# Power.net
KiCad netlist of a schematic drawn in Altium Designer
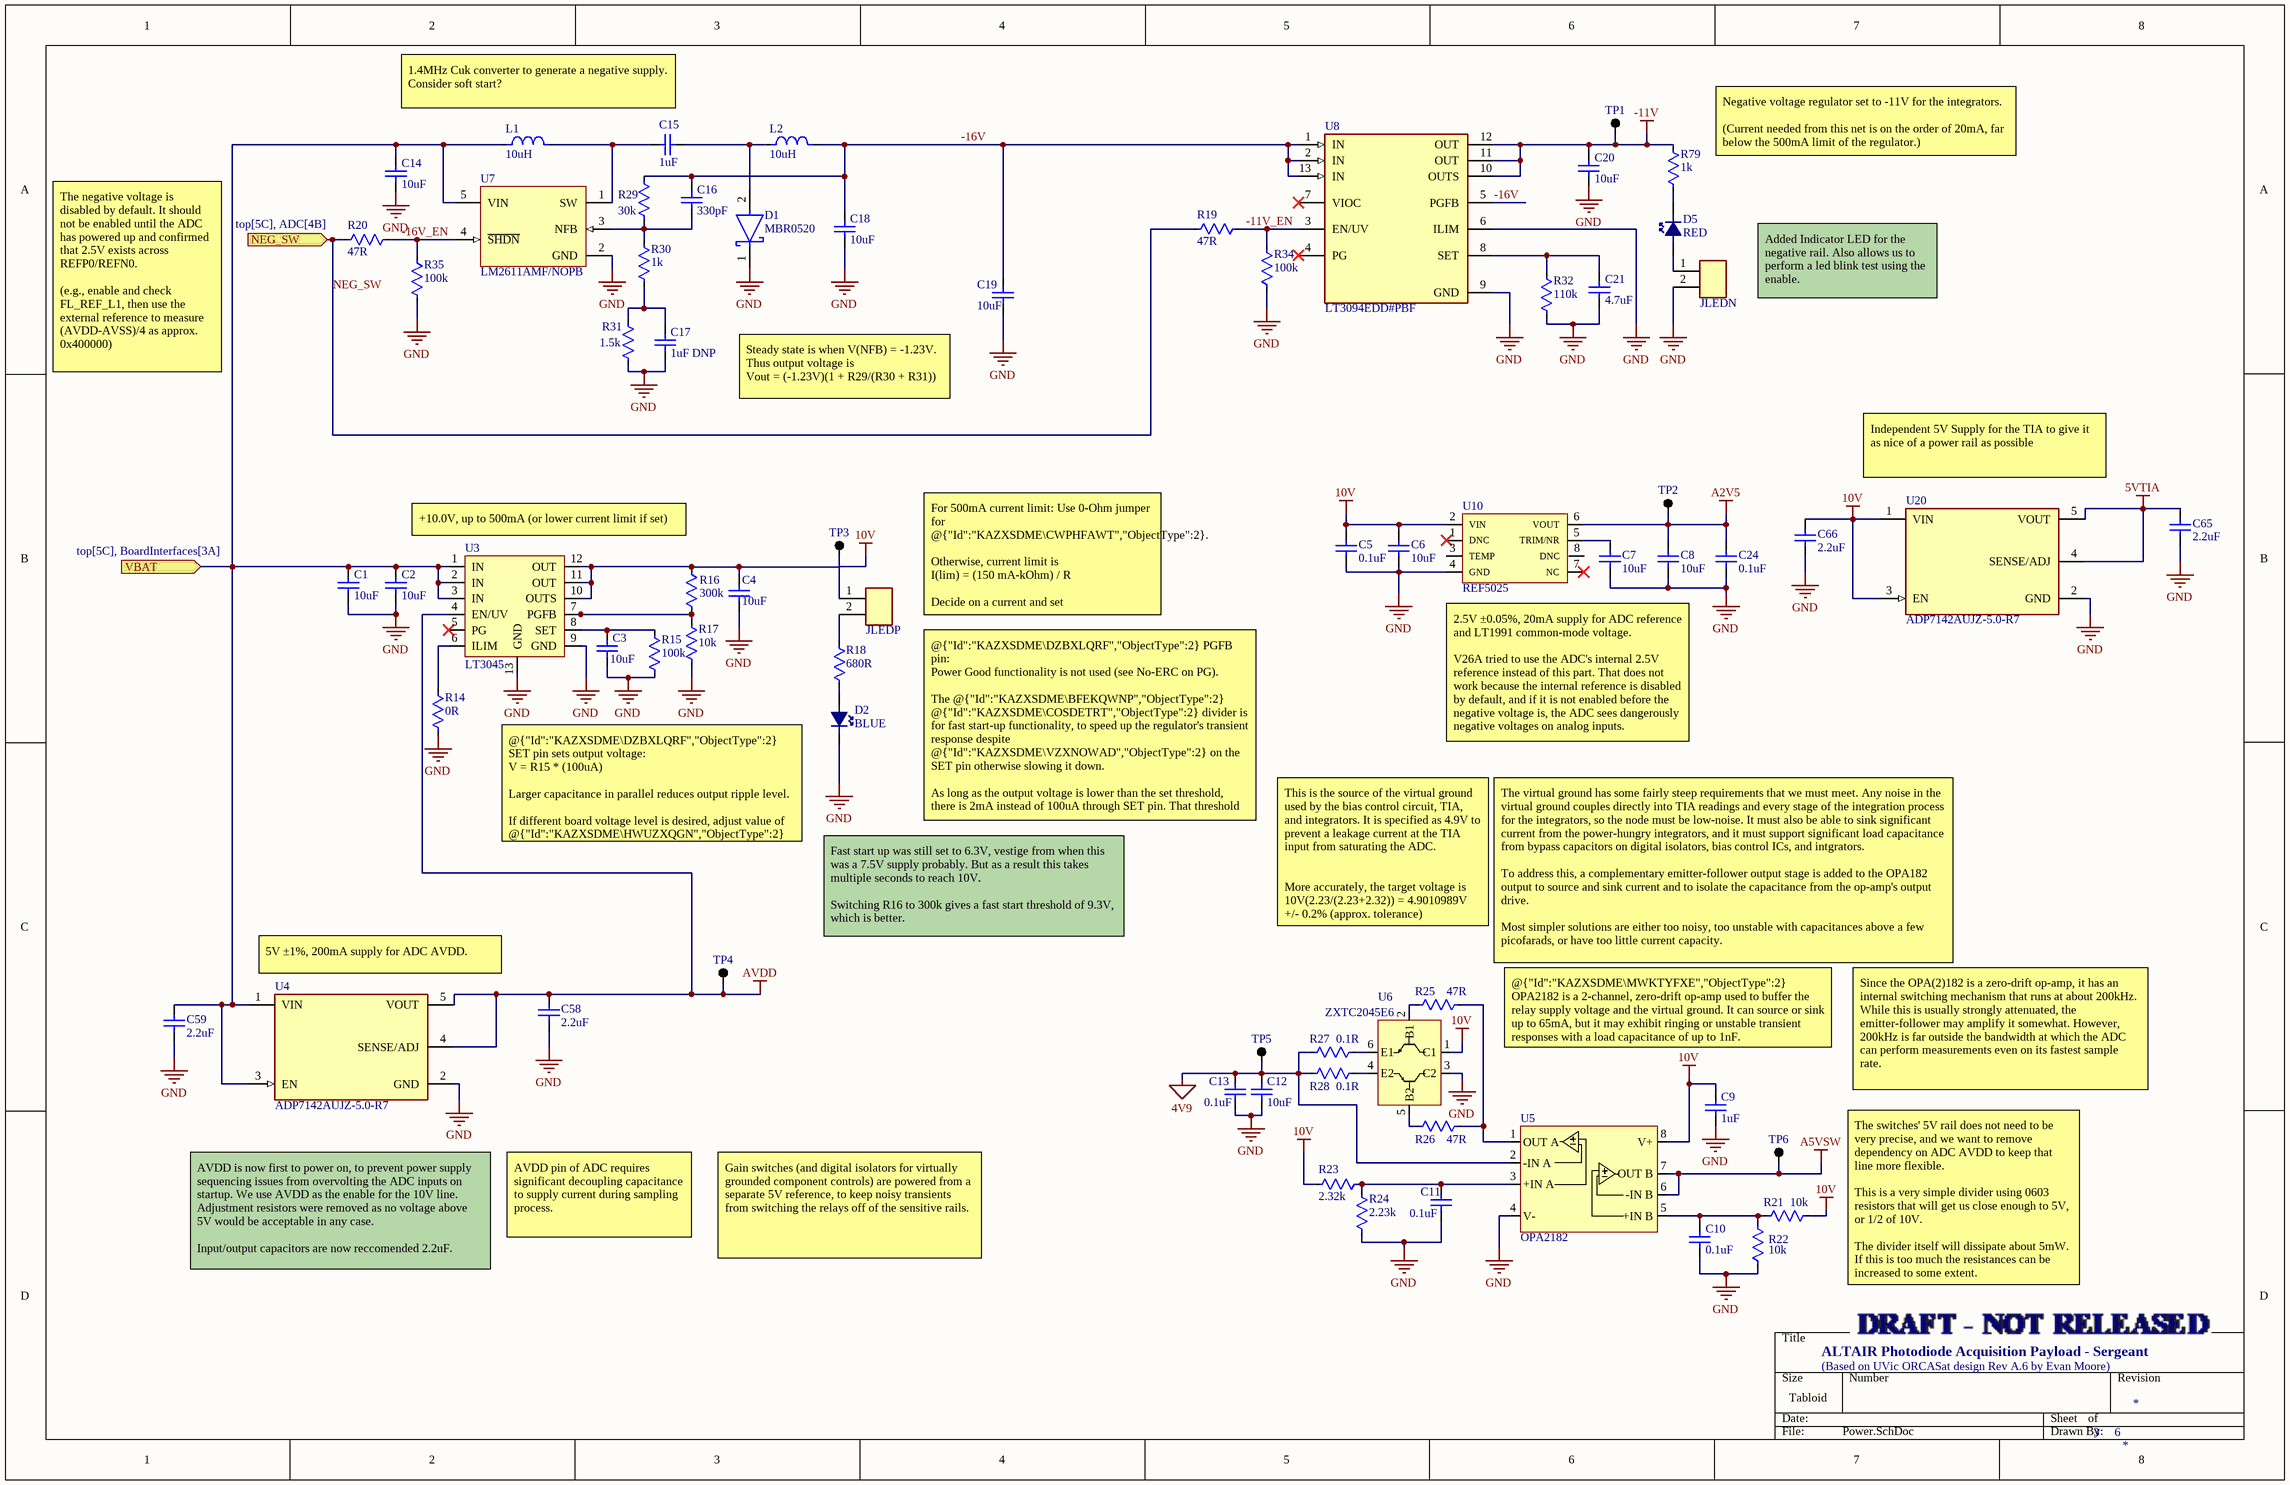
[diagram p0: Power.SchDoc]

(export (version "E")
  (design (tool "Eeschema 10.0.6"))
  (components
    (comp (ref "C1")
      (value "10uF")
      (footprint "CAP 1206 IPC LOW DENSITY")
      (description "Murata GRT319R6YA106KE01D - Cap Ceramic 10uF 35V X5R 10% Pad SMD 1206 85C Automotive T/R")
      (fields (field (name "MF") "Murata") (field (name "MP") "GRT319R6YA106KE01D"))
      (libsource (lib "ALTAIR_PD_Capacitors") (part "CAP"))
    )
    (comp (ref "C2")
      (value "10uF")
      (footprint "CAP 1206 IPC LOW DENSITY")
      (description "Murata GRT319R6YA106KE01D - Cap Ceramic 10uF 35V X5R 10% Pad SMD 1206 85C Automotive T/R")
      (fields (field (name "MF") "Murata") (field (name "MP") "GRT319R6YA106KE01D"))
      (libsource (lib "ALTAIR_PD_Capacitors") (part "CAP"))
    )
    (comp (ref "C3")
      (value "10uF")
      (footprint "CAP 1206 IPC LOW DENSITY")
      (description "Murata GRT319R6YA106KE01D - Cap Ceramic 10uF 35V X5R 10% Pad SMD 1206 85C Automotive T/R")
      (fields (field (name "MF") "Murata") (field (name "MP") "GRT319R6YA106KE01D"))
      (libsource (lib "ALTAIR_PD_Capacitors") (part "CAP"))
    )
    (comp (ref "C4")
      (value "10uF")
      (footprint "CAP 1206 IPC LOW DENSITY")
      (description "Murata GRT319R6YA106KE01D - Cap Ceramic 10uF 35V X5R 10% Pad SMD 1206 85C Automotive T/R")
      (fields (field (name "MF") "Murata") (field (name "MP") "GRT319R6YA106KE01D"))
      (libsource (lib "ALTAIR_PD_Capacitors") (part "CAP"))
    )
    (comp (ref "C5")
      (value "0.1uF")
      (footprint "CAP 0603 IPC MID DENSITY")
      (description "Kemet C0603C104K5RACAUTO - Cap Ceramic 0.1uF 50V X7R 10% 0603 125C Paper T/R")
      (fields (field (name "MF") "Kemet") (field (name "MP") "C0603C104K5RACAUTO"))
      (libsource (lib "ALTAIR_PD_Capacitors") (part "CAP"))
    )
    (comp (ref "C6")
      (value "10uF")
      (footprint "CAP 0805 IPC MID DENSITY")
      (description "Murata GRM21BR61E106KA73L - Cap Ceramic 10uF 10% 25V X5R 0805")
      (fields (field (name "MF") "Murata") (field (name "MP") "GRM21BR61E106KA73L"))
      (libsource (lib "ALTAIR_PD_Capacitors") (part "CAP"))
    )
    (comp (ref "C7")
      (value "10uF")
      (footprint "CAP 0805 IPC MID DENSITY")
      (description "Murata GRM21BR61E106KA73L - Cap Ceramic 10uF 10% 25V X5R 0805")
      (fields (field (name "MF") "Murata") (field (name "MP") "GRM21BR61E106KA73L"))
      (libsource (lib "ALTAIR_PD_Capacitors") (part "CAP"))
    )
    (comp (ref "C8")
      (value "10uF")
      (footprint "CAP 0805 IPC MID DENSITY")
      (description "Murata GRM21BR61E106KA73L - Cap Ceramic 10uF 10% 25V X5R 0805")
      (fields (field (name "MF") "Murata") (field (name "MP") "GRM21BR61E106KA73L"))
      (libsource (lib "ALTAIR_PD_Capacitors") (part "CAP"))
    )
    (comp (ref "C9")
      (value "1uF")
      (footprint "CAP 0603 IPC MID DENSITY")
      (description "Murata GRT188R61H105KE13D - Cap MLCC AEC-Q200 X5R 1uF 50V 0603")
      (fields (field (name "MF") "Murata") (field (name "MP") "GRT188R61H105KE13D"))
      (libsource (lib "ALTAIR_PD_Capacitors") (part "CAP"))
    )
    (comp (ref "C10")
      (value "0.1uF")
      (footprint "CAP 0603 IPC MID DENSITY")
      (description "Kemet C0603C104K5RACAUTO - Cap Ceramic 0.1uF 50V X7R 10% 0603 125C Paper T/R")
      (fields (field (name "MF") "Kemet") (field (name "MP") "C0603C104K5RACAUTO"))
      (libsource (lib "ALTAIR_PD_Capacitors") (part "CAP"))
    )
    (comp (ref "C11")
      (value "0.1uF")
      (footprint "CAP 0603 IPC MID DENSITY")
      (description "Kemet C0603C104K5RACAUTO - Cap Ceramic 0.1uF 50V X7R 10% 0603 125C Paper T/R")
      (fields (field (name "MF") "Kemet") (field (name "MP") "C0603C104K5RACAUTO"))
      (libsource (lib "ALTAIR_PD_Capacitors") (part "CAP"))
    )
    (comp (ref "C12")
      (value "10uF")
      (footprint "CAP 1206 IPC LOW DENSITY")
      (description "Murata GRT319R6YA106KE01D - Cap Ceramic 10uF 35V X5R 10% Pad SMD 1206 85C Automotive T/R")
      (fields (field (name "MF") "Murata") (field (name "MP") "GRT319R6YA106KE01D"))
      (libsource (lib "ALTAIR_PD_Capacitors") (part "CAP"))
    )
    (comp (ref "C13")
      (value "0.1uF")
      (footprint "CAP 0603 IPC MID DENSITY")
      (description "Kemet C0603C104K5RACAUTO - Cap Ceramic 0.1uF 50V X7R 10% 0603 125C Paper T/R")
      (fields (field (name "MF") "Kemet") (field (name "MP") "C0603C104K5RACAUTO"))
      (libsource (lib "ALTAIR_PD_Capacitors") (part "CAP"))
    )
    (comp (ref "C14")
      (value "10uF")
      (footprint "CAP 0805 IPC MID DENSITY")
      (description "Murata GRM21BR61E106KA73L - Cap Ceramic 10uF 10% 25V X5R 0805")
      (fields (field (name "MF") "Murata") (field (name "MP") "GRM21BR61E106KA73L"))
      (libsource (lib "ALTAIR_PD_Capacitors") (part "CAP"))
    )
    (comp (ref "C15")
      (value "1uF")
      (footprint "CAP 0603 IPC MID DENSITY")
      (description "Murata GRT188R61H105KE13D - Cap MLCC AEC-Q200 X5R 1uF 50V 0603")
      (fields (field (name "MF") "Murata") (field (name "MP") "GRT188R61H105KE13D"))
      (libsource (lib "ALTAIR_PD_Capacitors") (part "CAP"))
    )
    (comp (ref "C16")
      (value "330pF")
      (footprint "CAP 1206 NON-IPC KEMET NP0")
      (description "Kemet C1206C331J5GACTU - Cap Ceramic 330pF 50V 5% NP0 1206")
      (fields (field (name "MF") "Kemet") (field (name "MP") "C1206C331J5GACTU"))
      (libsource (lib "ALTAIR_PD_Capacitors") (part "CAP"))
    )
    (comp (ref "C17")
      (value "1uF DNP")
      (footprint "CAP 0603 IPC MID DENSITY")
      (description "Murata GRT188R61H105KE13D - Cap MLCC AEC-Q200 X5R 1uF 50V 0603")
      (fields (field (name "MF") "Murata") (field (name "MP") "GRT188R61H105KE13D"))
      (libsource (lib "ALTAIR_PD_Capacitors") (part "CAP"))
    )
    (comp (ref "C18")
      (value "10uF")
      (footprint "CAP 0805 IPC MID DENSITY")
      (description "Murata GRM21BR61E106KA73L - Cap Ceramic 10uF 10% 25V X5R 0805")
      (fields (field (name "MF") "Murata") (field (name "MP") "GRM21BR61E106KA73L"))
      (libsource (lib "ALTAIR_PD_Capacitors") (part "CAP"))
    )
    (comp (ref "C19")
      (value "10uF")
      (footprint "CAP 0805 IPC MID DENSITY")
      (description "Murata GRM21BR61E106KA73L - Cap Ceramic 10uF 10% 25V X5R 0805")
      (fields (field (name "MF") "Murata") (field (name "MP") "GRM21BR61E106KA73L"))
      (libsource (lib "ALTAIR_PD_Capacitors") (part "CAP"))
    )
    (comp (ref "C20")
      (value "10uF")
      (footprint "CAP 0805 IPC MID DENSITY")
      (description "Murata GRM21BR61E106KA73L - Cap Ceramic 10uF 10% 25V X5R 0805")
      (fields (field (name "MF") "Murata") (field (name "MP") "GRM21BR61E106KA73L"))
      (libsource (lib "ALTAIR_PD_Capacitors") (part "CAP"))
    )
    (comp (ref "C21")
      (value "4.7uF")
      (footprint "CAP 0805 NON-IPC KEMET X5R")
      (description "Kemet C0805C475K8PACTU - Cap Ceramic 4.7uF 10V X5R 0805")
      (fields (field (name "MF") "Kemet") (field (name "MP") "C0805C475K8PACTU"))
      (libsource (lib "ALTAIR_PD_Capacitors") (part "CAP"))
    )
    (comp (ref "C24")
      (value "0.1uF")
      (footprint "CAP 0603 IPC MID DENSITY")
      (description "Kemet C0603C104K5RACAUTO - Cap Ceramic 0.1uF 50V X7R 10% 0603 125C Paper T/R")
      (fields (field (name "MF") "Kemet") (field (name "MP") "C0603C104K5RACAUTO"))
      (libsource (lib "ALTAIR_PD_Capacitors") (part "CAP"))
    )
    (comp (ref "C58")
      (value "2.2uF")
      (footprint "CAP 1206 UNKNOWN")
      (description "Cap, Nonpolar, Any, Must choose footprint manually")
      (libsource (lib "ALTAIR_PD_Capacitors") (part "CAP"))
    )
    (comp (ref "C59")
      (value "2.2uF")
      (footprint "CAP 1206 UNKNOWN")
      (description "Cap, Nonpolar, Any, Must choose footprint manually")
      (libsource (lib "ALTAIR_PD_Capacitors") (part "CAP"))
    )
    (comp (ref "C65")
      (value "2.2uF")
      (footprint "CAP 1206 UNKNOWN")
      (description "Cap, Nonpolar, Any, Must choose footprint manually")
      (libsource (lib "ALTAIR_PD_Capacitors") (part "CAP"))
    )
    (comp (ref "C66")
      (value "2.2uF")
      (footprint "CAP 1206 UNKNOWN")
      (description "Cap, Nonpolar, Any, Must choose footprint manually")
      (libsource (lib "ALTAIR_PD_Capacitors") (part "CAP"))
    )
    (comp (ref "D1")
      (value "MBR0520")
      (footprint "SOD-123 ONSEMI SMALL PADS")
      (description "DIODE SCHOTTKY 20V 500MA SOD123")
      (fields (field (name "MF") "onsemi") (field (name "MP") "MBR0520LT1G"))
      (libsource (lib "ALTAIR_PD_Diodes") (part "Schottky"))
    )
    (comp (ref "D2")
      (value "BLUE")
      (footprint "LED 0603 MID DENSITY")
      (description "LED BLUE CLEAR 0603 SMD")
      (fields (field (name "MF") "Wurth Electronics") (field (name "MP") "150060BS75000"))
      (libsource (lib "ALTAIR_PD_Diodes") (part "LED-blue"))
    )
    (comp (ref "D5")
      (value "RED")
      (footprint "LED 0603 MID DENSITY")
      (description "LED BLUE CLEAR 0603 SMD")
      (fields (field (name "MF") "Wurth Electronics") (field (name "MP") "150060BS75000"))
      (libsource (lib "ALTAIR_PD_Diodes") (part "LED-blue"))
    )
    (comp (ref "JLEDN")
      (value "JLED")
      (footprint "JUMPER 2POS 1MM PITCH THT")
      (description "2x1 Header THT 1mm Pitch")
      (fields
        (field (name "MF") "GCT (GLOBAL CONNECTOR TECHNOLOGY)")
        (field (name "MP") "BC020-02-A-0200-0300-L-G")
      )
      (libsource (lib "ALTAIR_PD_Headers") (part "BC020-02-A-0200-0300-L-G"))
    )
    (comp (ref "JLEDP")
      (value "JLED")
      (footprint "ALTAIR_PD_Headers:JUMPER 2POS 1MM PITCH THT")
      (description "2x1 Header THT 1mm Pitch")
      (fields
        (field (name "MF") "GCT (GLOBAL CONNECTOR TECHNOLOGY)")
        (field (name "MP") "BC020-02-A-0200-0300-L-G")
      )
      (libsource (lib "ALTAIR_PD_Headers") (part "BC020-02-A-0200-0300-L-G"))
    )
    (comp (ref "L1")
      (value "10uH")
      (footprint "IND VLS3012CX-1 NONSTANDARD TDK")
      (description "TDK VLS3012CX-100M-1 - Inductor 10uH 20% 1.25A 0.324Ohm NonstandardPkg")
      (fields (field (name "TOLERANCE") "20%") (field (name "MF") "TDK Corporation"))
      (libsource (lib "ALTAIR_PD_Inductors") (part "IND"))
    )
    (comp (ref "L2")
      (value "10uH")
      (footprint "IND VLS3012CX-1 NONSTANDARD TDK")
      (description "TDK VLS3012CX-100M-1 - Inductor 10uH 20% 1.25A 0.324Ohm NonstandardPkg")
      (fields (field (name "TOLERANCE") "20%") (field (name "MF") "TDK Corporation"))
      (libsource (lib "ALTAIR_PD_Inductors") (part "IND"))
    )
    (comp (ref "R14")
      (value "0R")
      (footprint "RES 0603 IPC MID DENSITY")
      (description "Vishay CRCW06030000Z0EA - Res 0 Ohms 1/8W SMD 0603")
      (fields (field (name "MF") "Vishay Dale") (field (name "MP") "CRCW06030000Z0EA"))
      (libsource (lib "ALTAIR_PD_Resistors") (part "RES"))
    )
    (comp (ref "R15")
      (value "100k")
      (footprint "RES 0603 IPC MID DENSITY")
      (description "Panasonic ERA-3ARB104V - Res SMD 0603 0.1% 0.10W T.C. 10ppm 100K")
      (fields (field (name "MF") "Panasonic Electronic Components") (field (name "MP") "ERA-3ARB104V"))
      (libsource (lib "ALTAIR_PD_Resistors") (part "RES"))
    )
    (comp (ref "R16")
      (value "300k")
      (footprint "RES 0603 IPC MID DENSITY")
      (description "Vishay MCT06030C2003FP500 - Res SMD 200kOhm 1% 1/10W 0603")
      (fields (field (name "MF") "Vishay Dale") (field (name "MP") "MCT06030C2003FP500"))
      (libsource (lib "ALTAIR_PD_Resistors") (part "RES"))
    )
    (comp (ref "R17")
      (value "10k")
      (footprint "RES 0603 IPC MID DENSITY")
      (description "Vishay CRCW060310K0FKEA SMD 0603 10k, CRCW e3 Series, 75V, thick film, 100mW")
      (fields (field (name "MF") "Vishay Dale") (field (name "MP") "CRCW060310K0FKEA"))
      (libsource (lib "ALTAIR_PD_Resistors") (part "RES"))
    )
    (comp (ref "R18")
      (value "680R")
      (footprint "RES 0603 IPC MID DENSITY")
      (description "Panasonic ERJ-3EKF6800V - Res SMD 680 Ohm 1% 1/10W 0603")
      (fields (field (name "MF") "Panasonic Electronic Components") (field (name "MP") "ERJ-3EKF6800V"))
      (libsource (lib "ALTAIR_PD_Resistors") (part "RES"))
    )
    (comp (ref "R19")
      (value "47R")
      (footprint "RES 0603 IPC MID DENSITY")
      (description "Vishay CRCW060347R0JNEA - Res 47Ohm 5% 1/8W SMD 0603")
      (fields (field (name "MF") "Vishay Dale") (field (name "MP") "CRCW060347R0JNEA"))
      (libsource (lib "ALTAIR_PD_Resistors") (part "RES"))
    )
    (comp (ref "R20")
      (value "47R")
      (footprint "RES 0603 IPC MID DENSITY")
      (description "Vishay CRCW060347R0JNEA - Res 47Ohm 5% 1/8W SMD 0603")
      (fields (field (name "MF") "Vishay Dale") (field (name "MP") "CRCW060347R0JNEA"))
      (libsource (lib "ALTAIR_PD_Resistors") (part "RES"))
    )
    (comp (ref "R21")
      (value "10k")
      (footprint "RES 0603 IPC MID DENSITY")
      (description "Vishay CRCW060310K0FKEA SMD 0603 10k, CRCW e3 Series, 75V, thick film, 100mW")
      (fields (field (name "MF") "Vishay Dale") (field (name "MP") "CRCW060310K0FKEA"))
      (libsource (lib "ALTAIR_PD_Resistors") (part "RES"))
    )
    (comp (ref "R22")
      (value "10k")
      (footprint "RES 0603 IPC MID DENSITY")
      (description "Vishay CRCW060310K0FKEA SMD 0603 10k, CRCW e3 Series, 75V, thick film, 100mW")
      (fields (field (name "MF") "Vishay Dale") (field (name "MP") "CRCW060310K0FKEA"))
      (libsource (lib "ALTAIR_PD_Resistors") (part "RES"))
    )
    (comp (ref "R23")
      (value "2.32k")
      (footprint "RES 0603 IPC MID DENSITY")
      (description "Vishay TNPW06032K32BEEA - Res 2.32k 0.1% 0.21W SMD 0603")
      (fields (field (name "MF") "Vishay Dale") (field (name "MP") "TNPW06032K32BEEA"))
      (libsource (lib "ALTAIR_PD_Resistors") (part "RES"))
    )
    (comp (ref "R24")
      (value "2.23k")
      (footprint "RES 0603 IPC MID DENSITY")
      (description "KOA Speer RN73R1JTTD2231B25 - Res 2.23k 0.1% 1/10W SMD 0603")
      (fields (field (name "MF") "KOA Speer Electronics, Inc.") (field (name "MP") "RN73R1JTTD2231B25"))
      (libsource (lib "ALTAIR_PD_Resistors") (part "RES"))
    )
    (comp (ref "R25")
      (value "47R")
      (footprint "RES 0402 NON-IPC SEI")
      (description "Stackpole RMCF0402JT47R0 - Res 47Ohm 5% 0.063W 0402 Thick Film AEC-Q200 compliant")
      (fields (field (name "MF") "Stackpole Electronics Inc.") (field (name "MP") "RMCF0402JT47R0"))
      (libsource (lib "ALTAIR_PD_Resistors") (part "RES"))
    )
    (comp (ref "R26")
      (value "47R")
      (footprint "RES 0402 NON-IPC SEI")
      (description "Stackpole RMCF0402JT47R0 - Res 47Ohm 5% 0.063W 0402 Thick Film AEC-Q200 compliant")
      (fields (field (name "MF") "Stackpole Electronics Inc.") (field (name "MP") "RMCF0402JT47R0"))
      (libsource (lib "ALTAIR_PD_Resistors") (part "RES"))
    )
    (comp (ref "R27")
      (value "0.1R")
      (footprint "RES 0402 NON-IPC YAGEO")
      (description "Yageo RL0402JR-070R1L - Res 0.1Ohm 5% 1/16W SMD 0402")
      (fields (field (name "MF") "YAGEO") (field (name "MP") "RL0402JR-070R1L"))
      (libsource (lib "ALTAIR_PD_Resistors") (part "RES"))
    )
    (comp (ref "R28")
      (value "0.1R")
      (footprint "RES 0402 NON-IPC YAGEO")
      (description "Yageo RL0402JR-070R1L - Res 0.1Ohm 5% 1/16W SMD 0402")
      (fields (field (name "MF") "YAGEO") (field (name "MP") "RL0402JR-070R1L"))
      (libsource (lib "ALTAIR_PD_Resistors") (part "RES"))
    )
    (comp (ref "R29")
      (value "30k")
      (footprint "RES 0805 IPC HIGH DENSITY")
      (description "Panasonic ERA-6AEB303V - Res 30kOhm 0.1% 1/8W 0805")
      (fields (field (name "MF") "Panasonic Electronic Components") (field (name "MP") "ERA-6AEB303V"))
      (libsource (lib "ALTAIR_PD_Resistors") (part "RES"))
    )
    (comp (ref "R30")
      (value "1k")
      (footprint "RES 0402 IPC LOW DENSITY YAGEO")
      (description "Yageo RC0402FR-071KL - Res 1kOhm 1% 1/16W 0402")
      (fields (field (name "MF") "YAGEO") (field (name "MP") "RC0402FR-071KL"))
      (libsource (lib "ALTAIR_PD_Resistors") (part "RES"))
    )
    (comp (ref "R31")
      (value "1.5k")
      (footprint "RES 1206 NON-IPC VISHAY")
      (description "Vishay TNPU12061K50BZEN00 - Res 1.5kOhm 0.1% 1/4W 1206")
      (fields (field (name "MF") "Vishay Dale") (field (name "MP") "TNPU12061K50BZEN00"))
      (libsource (lib "ALTAIR_PD_Resistors") (part "RES"))
    )
    (comp (ref "R32")
      (value "110k")
      (footprint "RES 0603 IPC MID DENSITY")
      (description "Panasonic ERA-3AEB114V - Res 110k 0.1% 1/10W SMD 0603")
      (fields (field (name "MF") "Panasonic Electronic Components") (field (name "MP") "ERA-3AEB114V"))
      (libsource (lib "ALTAIR_PD_Resistors") (part "RES"))
    )
    (comp (ref "R34")
      (value "100k")
      (footprint "RES 0603 IPC MID DENSITY")
      (description "Panasonic ERJ-3GEYJ104V - Res 100k 5% 1/10W SMD 0603")
      (fields (field (name "MF") "Panasonic Electronic Components") (field (name "MP") "ERJ-3GEYJ104V"))
      (libsource (lib "ALTAIR_PD_Resistors") (part "RES"))
    )
    (comp (ref "R35")
      (value "100k")
      (footprint "RES 0603 IPC MID DENSITY")
      (description "Panasonic ERJ-3GEYJ104V - Res 100k 5% 1/10W SMD 0603")
      (fields (field (name "MF") "Panasonic Electronic Components") (field (name "MP") "ERJ-3GEYJ104V"))
      (libsource (lib "ALTAIR_PD_Resistors") (part "RES"))
    )
    (comp (ref "R79")
      (value "1k")
      (footprint "RES 0603 IPC MID DENSITY")
      (description "Panasonic ERJ-3EKF6800V - Res SMD 680 Ohm 1% 1/10W 0603")
      (fields (field (name "MF") "Panasonic Electronic Components") (field (name "MP") "ERJ-3EKF6800V"))
      (libsource (lib "ALTAIR_PD_Resistors") (part "RES"))
    )
    (comp (ref "TP1")
      (value "Testpoint")
      (footprint "TESTPOINT THT")
      (libsource (lib "ALTAIR_PD_Testpoint") (part "Testpoint"))
    )
    (comp (ref "TP2")
      (value "Testpoint")
      (footprint "TESTPOINT THT")
      (libsource (lib "ALTAIR_PD_Testpoint") (part "Testpoint"))
    )
    (comp (ref "TP3")
      (value "Testpoint")
      (footprint "TESTPOINT THT")
      (libsource (lib "ALTAIR_PD_Testpoint") (part "Testpoint"))
    )
    (comp (ref "TP4")
      (value "Testpoint")
      (footprint "TESTPOINT THT")
      (libsource (lib "ALTAIR_PD_Testpoint") (part "Testpoint"))
    )
    (comp (ref "TP5")
      (value "Testpoint")
      (footprint "TESTPOINT THT")
      (libsource (lib "ALTAIR_PD_Testpoint") (part "Testpoint"))
    )
    (comp (ref "TP6")
      (value "Testpoint")
      (footprint "TESTPOINT THT")
      (libsource (lib "ALTAIR_PD_Testpoint") (part "Testpoint"))
    )
    (comp (ref "U3")
      (value "LT3045")
      (footprint "12-TSOP 0.65MM PITCH 3MM WIDTH EP IPC MID DENSITY")
      (description "20V 500mA Ultralow Noise Ultrahigh PSRR Adjustable Linear Regulator 260V Dropout MSOP-12")
      (fields (field (name "MF") "Analog Devices / Linear Technology") (field (name "MP") "LT3045EMSE#PBF"))
      (libsource (lib "ALTAIR_PD_Regulators") (part "LT3045"))
    )
    (comp (ref "U4")
      (value "ADP7142AUJZ-5.0-R7")
      (footprint "SOT23-5 HIGH DENSITY AD")
      (description "1.2-40V 200mA Low Noise CMOS LDO Adjustable Linear Regulator TSOT23")
      (fields
        (field (name "OCTOPART") "https://octopart.com/adp7142aujz-r7-analog+devices-38928114")
        (field (name "MF") "Analog Devices")
      )
      (libsource (lib "ALTAIR_PD_Regulators") (part "ADP7142AUJZ-R7"))
    )
    (comp (ref "U5")
      (value "OPA2182")
      (footprint "8-TSSOP 0.65MM PITCH 4.4MM WIDTH IPC MID DENSITY")
      (fields (field (name "MF") "Texas Instruments") (field (name "MP") "OPA2182IDGKR"))
      (libsource (lib "ALTAIR_PD_Amplifiers") (part "OPA2182IDBV"))
    )
    (comp (ref "U6")
      (value "ZXTC2045E6")
      (footprint "SOT23-6 NON-IPC DIODES")
      (description "BJT Array, 1NPN 1PNP, VCE(sat) 375mV, hFE 300, Breakdown 30V, 6-SOT-23")
      (fields (field (name "MF") "Diodes Incorporated") (field (name "MP") "ZXTC2045E6TA"))
      (libsource (lib "ALTAIR_PD_BJTs") (part "ZXTC2045E6"))
    )
    (comp (ref "U7")
      (value "LM2611AMF/NOPB")
      (footprint "SOT23-5 MID DENSITY")
      (description "1.4MHz Cuk Converter, 5-pin SOT-23, Pb-Free")
      (fields (field (name "MF") "Texas Instruments"))
      (libsource (lib "ALTAIR_PD_Converters") (part "LM2611AMF"))
    )
    (comp (ref "U8")
      (value "LT3094EDD#PBF")
      (footprint "12DFN 3x3MM EP IPC MID DENSITY")
      (description "-20V 500mA Ultralow Noise Ultrahigh PSRR Adjustable Negative Linear Regulator 12DFN")
      (fields (field (name "MF") "Analog Devices"))
      (libsource (lib "ALTAIR_PD_Regulators") (part "LT3094EDD#PBF"))
    )
    (comp (ref "U10")
      (value "REF5025")
      (footprint "8-TSOP 0.65MM PITCH 3MM WIDTH IPC MID DENSITY")
      (description "2.5V±0.05% Voltage Reference 8VSSOP")
      (fields (field (name "MF") "Texas Instruments") (field (name "MP") "REF5025IDGKR"))
      (libsource (lib "ALTAIR_PD_MiscPower") (part "REF5050IDGKR"))
    )
    (comp (ref "U20")
      (value "ADP7142AUJZ-5.0-R7")
      (footprint "SOT23-5 HIGH DENSITY AD")
      (description "1.2-40V 200mA Low Noise CMOS LDO Adjustable Linear Regulator TSOT23")
      (fields
        (field (name "OCTOPART") "https://octopart.com/adp7142aujz-r7-analog+devices-38928114")
        (field (name "MF") "Analog Devices")
      )
      (libsource (lib "ALTAIR_PD_Regulators") (part "ADP7142AUJZ-R7"))
    )
  )
  (nets
    (net (code "1") (name "-11V") (class "Default")
      (node (ref "C20") (pin "1") (pinfunction "1_1") (pintype "passive"))
      (node (ref "R79") (pin "2") (pinfunction "2_2") (pintype "passive"))
      (node (ref "TP1") (pin "1") (pinfunction "1_1") (pintype "passive"))
      (node (ref "U8") (pin "10") (pinfunction "OUTS_10") (pintype "power_in"))
      (node (ref "U8") (pin "11") (pinfunction "OUT_11") (pintype "power_in"))
      (node (ref "U8") (pin "12") (pinfunction "OUT_12") (pintype "power_in"))
    )
    (net (code "2") (name "/-11V_EN") (class "Default")
      (node (ref "R19") (pin "1") (pinfunction "1_1") (pintype "passive"))
      (node (ref "R34") (pin "1") (pinfunction "1_1") (pintype "passive"))
      (node (ref "U8") (pin "3") (pinfunction "EN/UV_3") (pintype "passive"))
    )
    (net (code "3") (name "/-16V") (class "Default")
      (node (ref "C16") (pin "1") (pinfunction "1_1") (pintype "passive"))
      (node (ref "C18") (pin "1") (pinfunction "1_1") (pintype "passive"))
      (node (ref "C19") (pin "1") (pinfunction "1_1") (pintype "passive"))
      (node (ref "L2") (pin "2") (pinfunction "2_2") (pintype "passive"))
      (node (ref "R29") (pin "2") (pinfunction "2_2") (pintype "passive"))
      (node (ref "U8") (pin "1") (pinfunction "IN_1") (pintype "input"))
      (node (ref "U8") (pin "13") (pinfunction "IN_13") (pintype "input"))
      (node (ref "U8") (pin "2") (pinfunction "IN_2") (pintype "input"))
      (node (ref "U8") (pin "5") (pinfunction "PGFB_5") (pintype "passive"))
    )
    (net (code "4") (name "/-16V_EN") (class "Default")
      (node (ref "R20") (pin "1") (pinfunction "1_1") (pintype "passive"))
      (node (ref "R35") (pin "1") (pinfunction "1_1") (pintype "passive"))
      (node (ref "U7") (pin "4") (pinfunction "~{SHDN}_4") (pintype "input"))
    )
    (net (code "5") (name "/NEG_SW") (class "Default")
      (node (ref "R19") (pin "2") (pinfunction "2_2") (pintype "passive"))
      (node (ref "R20") (pin "2") (pinfunction "2_2") (pintype "passive"))
    )
    (net (code "6") (name "/VBAT") (class "Default")
      (node (ref "C1") (pin "2") (pinfunction "2_2") (pintype "passive"))
      (node (ref "C14") (pin "2") (pinfunction "2_2") (pintype "passive"))
      (node (ref "C2") (pin "2") (pinfunction "2_2") (pintype "passive"))
      (node (ref "C59") (pin "1") (pinfunction "1_1") (pintype "passive"))
      (node (ref "L1") (pin "1") (pinfunction "1_1") (pintype "passive"))
      (node (ref "U3") (pin "1") (pinfunction "IN_1") (pintype "passive"))
      (node (ref "U3") (pin "2") (pinfunction "IN_2") (pintype "passive"))
      (node (ref "U3") (pin "3") (pinfunction "IN_3") (pintype "passive"))
      (node (ref "U4") (pin "1") (pinfunction "VIN_1") (pintype "power_in"))
      (node (ref "U4") (pin "3") (pinfunction "EN_3") (pintype "input"))
      (node (ref "U7") (pin "5") (pinfunction "VIN_5") (pintype "power_in"))
    )
    (net (code "7") (name "4V9") (class "Default")
      (node (ref "C12") (pin "2") (pinfunction "2_2") (pintype "passive"))
      (node (ref "C13") (pin "2") (pinfunction "2_2") (pintype "passive"))
      (node (ref "R27") (pin "1") (pinfunction "1_1") (pintype "passive"))
      (node (ref "R28") (pin "1") (pinfunction "1_1") (pintype "passive"))
      (node (ref "TP5") (pin "1") (pinfunction "1_1") (pintype "passive"))
      (node (ref "U5") (pin "2") (pinfunction "-IN_A_2") (pintype "passive"))
    )
    (net (code "8") (name "5VTIA") (class "Default")
      (node (ref "C65") (pin "1") (pinfunction "1_1") (pintype "passive"))
      (node (ref "U20") (pin "4") (pinfunction "SENSE/ADJ_4") (pintype "passive"))
      (node (ref "U20") (pin "5") (pinfunction "VOUT_5") (pintype "passive"))
    )
    (net (code "9") (name "10V") (class "Default")
      (node (ref "C4") (pin "2") (pinfunction "2_2") (pintype "passive"))
      (node (ref "C5") (pin "1") (pinfunction "1_1") (pintype "passive"))
      (node (ref "C6") (pin "2") (pinfunction "2_2") (pintype "passive"))
      (node (ref "C66") (pin "1") (pinfunction "1_1") (pintype "passive"))
      (node (ref "C9") (pin "2") (pinfunction "2_2") (pintype "passive"))
      (node (ref "JLEDP") (pin "1") (pinfunction "1_1") (pintype "passive"))
      (node (ref "R16") (pin "2") (pinfunction "2_2") (pintype "passive"))
      (node (ref "R21") (pin "2") (pinfunction "2_2") (pintype "passive"))
      (node (ref "R23") (pin "2") (pinfunction "2_2") (pintype "passive"))
      (node (ref "TP3") (pin "1") (pinfunction "1_1") (pintype "passive"))
      (node (ref "U10") (pin "2") (pinfunction "VIN_2") (pintype "passive"))
      (node (ref "U20") (pin "1") (pinfunction "VIN_1") (pintype "power_in"))
      (node (ref "U20") (pin "3") (pinfunction "EN_3") (pintype "input"))
      (node (ref "U3") (pin "10") (pinfunction "OUTS_10") (pintype "passive"))
      (node (ref "U3") (pin "11") (pinfunction "OUT_11") (pintype "passive"))
      (node (ref "U3") (pin "12") (pinfunction "OUT_12") (pintype "passive"))
      (node (ref "U5") (pin "8") (pinfunction "V+_8") (pintype "passive"))
      (node (ref "U6") (pin "1") (pinfunction "C1_1") (pintype "passive"))
    )
    (net (code "10") (name "A2V5") (class "Default")
      (node (ref "C24") (pin "1") (pinfunction "1_1") (pintype "passive"))
      (node (ref "C8") (pin "2") (pinfunction "2_2") (pintype "passive"))
      (node (ref "TP2") (pin "1") (pinfunction "1_1") (pintype "passive"))
      (node (ref "U10") (pin "6") (pinfunction "VOUT_6") (pintype "passive"))
    )
    (net (code "11") (name "A5VSW") (class "Default")
      (node (ref "TP6") (pin "1") (pinfunction "1_1") (pintype "passive"))
      (node (ref "U5") (pin "6") (pinfunction "-IN_B_6") (pintype "passive"))
      (node (ref "U5") (pin "7") (pinfunction "OUT_B_7") (pintype "passive"))
    )
    (net (code "12") (name "AVDD") (class "Default")
      (node (ref "C58") (pin "1") (pinfunction "1_1") (pintype "passive"))
      (node (ref "TP4") (pin "1") (pinfunction "1_1") (pintype "passive"))
      (node (ref "U3") (pin "4") (pinfunction "EN/UV_4") (pintype "passive"))
      (node (ref "U4") (pin "4") (pinfunction "SENSE/ADJ_4") (pintype "passive"))
      (node (ref "U4") (pin "5") (pinfunction "VOUT_5") (pintype "passive"))
    )
    (net (code "13") (name "GND") (class "Default")
      (node (ref "C1") (pin "1") (pinfunction "1_1") (pintype "passive"))
      (node (ref "C10") (pin "1") (pinfunction "1_1") (pintype "passive"))
      (node (ref "C11") (pin "1") (pinfunction "1_1") (pintype "passive"))
      (node (ref "C12") (pin "1") (pinfunction "1_1") (pintype "passive"))
      (node (ref "C13") (pin "1") (pinfunction "1_1") (pintype "passive"))
      (node (ref "C14") (pin "1") (pinfunction "1_1") (pintype "passive"))
      (node (ref "C17") (pin "2") (pinfunction "2_2") (pintype "passive"))
      (node (ref "C18") (pin "2") (pinfunction "2_2") (pintype "passive"))
      (node (ref "C19") (pin "2") (pinfunction "2_2") (pintype "passive"))
      (node (ref "C2") (pin "1") (pinfunction "1_1") (pintype "passive"))
      (node (ref "C20") (pin "2") (pinfunction "2_2") (pintype "passive"))
      (node (ref "C21") (pin "2") (pinfunction "2_2") (pintype "passive"))
      (node (ref "C24") (pin "2") (pinfunction "2_2") (pintype "passive"))
      (node (ref "C3") (pin "1") (pinfunction "1_1") (pintype "passive"))
      (node (ref "C4") (pin "1") (pinfunction "1_1") (pintype "passive"))
      (node (ref "C5") (pin "2") (pinfunction "2_2") (pintype "passive"))
      (node (ref "C58") (pin "2") (pinfunction "2_2") (pintype "passive"))
      (node (ref "C59") (pin "2") (pinfunction "2_2") (pintype "passive"))
      (node (ref "C6") (pin "1") (pinfunction "1_1") (pintype "passive"))
      (node (ref "C65") (pin "2") (pinfunction "2_2") (pintype "passive"))
      (node (ref "C66") (pin "2") (pinfunction "2_2") (pintype "passive"))
      (node (ref "C7") (pin "2") (pinfunction "2_2") (pintype "passive"))
      (node (ref "C8") (pin "1") (pinfunction "1_1") (pintype "passive"))
      (node (ref "C9") (pin "1") (pinfunction "1_1") (pintype "passive"))
      (node (ref "D1") (pin "1") (pinfunction "C_1") (pintype "passive"))
      (node (ref "D2") (pin "1") (pinfunction "1_1") (pintype "passive"))
      (node (ref "JLEDN") (pin "2") (pinfunction "2_2") (pintype "passive"))
      (node (ref "R14") (pin "1") (pinfunction "1_1") (pintype "passive"))
      (node (ref "R15") (pin "1") (pinfunction "1_1") (pintype "passive"))
      (node (ref "R17") (pin "1") (pinfunction "1_1") (pintype "passive"))
      (node (ref "R22") (pin "1") (pinfunction "1_1") (pintype "passive"))
      (node (ref "R24") (pin "1") (pinfunction "1_1") (pintype "passive"))
      (node (ref "R31") (pin "1") (pinfunction "1_1") (pintype "passive"))
      (node (ref "R32") (pin "2") (pinfunction "2_2") (pintype "passive"))
      (node (ref "R34") (pin "2") (pinfunction "2_2") (pintype "passive"))
      (node (ref "R35") (pin "2") (pinfunction "2_2") (pintype "passive"))
      (node (ref "U10") (pin "4") (pinfunction "GND_4") (pintype "passive"))
      (node (ref "U20") (pin "2") (pinfunction "GND_2") (pintype "power_in"))
      (node (ref "U3") (pin "13") (pinfunction "GND_13") (pintype "passive"))
      (node (ref "U3") (pin "9") (pinfunction "GND_9") (pintype "passive"))
      (node (ref "U4") (pin "2") (pinfunction "GND_2") (pintype "power_in"))
      (node (ref "U5") (pin "4") (pinfunction "V-_4") (pintype "passive"))
      (node (ref "U6") (pin "3") (pinfunction "C2_3") (pintype "passive"))
      (node (ref "U7") (pin "2") (pinfunction "GND_2") (pintype "power_in"))
      (node (ref "U8") (pin "6") (pinfunction "ILIM_6") (pintype "passive"))
      (node (ref "U8") (pin "9") (pinfunction "GND_9") (pintype "power_in"))
    )
    (net (code "14") (name "Net-(C17-Pad1)") (class "Default")
      (node (ref "C17") (pin "1") (pinfunction "1_1") (pintype "passive"))
      (node (ref "R30") (pin "1") (pinfunction "1_1") (pintype "passive"))
      (node (ref "R31") (pin "2") (pinfunction "2_2") (pintype "passive"))
    )
    (net (code "15") (name "Net-(D1-A)") (class "Default")
      (node (ref "C15") (pin "2") (pinfunction "2_2") (pintype "passive"))
      (node (ref "D1") (pin "2") (pinfunction "A_2") (pintype "passive"))
      (node (ref "L2") (pin "1") (pinfunction "1_1") (pintype "passive"))
    )
    (net (code "16") (name "Net-(D2-Pad2)") (class "Default")
      (node (ref "D2") (pin "2") (pinfunction "2_2") (pintype "passive"))
      (node (ref "R18") (pin "1") (pinfunction "1_1") (pintype "passive"))
    )
    (net (code "17") (name "Net-(D5-Pad1)") (class "Default")
      (node (ref "D5") (pin "1") (pinfunction "1_1") (pintype "passive"))
      (node (ref "R79") (pin "1") (pinfunction "1_1") (pintype "passive"))
    )
    (net (code "18") (name "Net-(D5-Pad2)") (class "Default")
      (node (ref "D5") (pin "2") (pinfunction "2_2") (pintype "passive"))
      (node (ref "JLEDN") (pin "1") (pinfunction "1_1") (pintype "passive"))
    )
    (net (code "19") (name "Net-(JLEDP-Pad2)") (class "Default")
      (node (ref "JLEDP") (pin "2") (pinfunction "2_2") (pintype "passive"))
      (node (ref "R18") (pin "2") (pinfunction "2_2") (pintype "passive"))
    )
    (net (code "20") (name "Net-(U3-ILIM)") (class "Default")
      (node (ref "R14") (pin "2") (pinfunction "2_2") (pintype "passive"))
      (node (ref "U3") (pin "6") (pinfunction "ILIM_6") (pintype "passive"))
    )
    (net (code "21") (name "Net-(U3-PGFB)") (class "Default")
      (node (ref "R16") (pin "1") (pinfunction "1_1") (pintype "passive"))
      (node (ref "R17") (pin "2") (pinfunction "2_2") (pintype "passive"))
      (node (ref "U3") (pin "7") (pinfunction "PGFB_7") (pintype "passive"))
    )
    (net (code "22") (name "Net-(U3-SET)") (class "Default")
      (node (ref "C3") (pin "2") (pinfunction "2_2") (pintype "passive"))
      (node (ref "R15") (pin "2") (pinfunction "2_2") (pintype "passive"))
      (node (ref "U3") (pin "8") (pinfunction "SET_8") (pintype "passive"))
    )
    (net (code "23") (name "Net-(U5-+IN_A)") (class "Default")
      (node (ref "C11") (pin "2") (pinfunction "2_2") (pintype "passive"))
      (node (ref "R23") (pin "1") (pinfunction "1_1") (pintype "passive"))
      (node (ref "R24") (pin "2") (pinfunction "2_2") (pintype "passive"))
      (node (ref "U5") (pin "3") (pinfunction "+IN_A_3") (pintype "passive"))
    )
    (net (code "24") (name "Net-(U5-+IN_B)") (class "Default")
      (node (ref "C10") (pin "2") (pinfunction "2_2") (pintype "passive"))
      (node (ref "R21") (pin "1") (pinfunction "1_1") (pintype "passive"))
      (node (ref "R22") (pin "2") (pinfunction "2_2") (pintype "passive"))
      (node (ref "U5") (pin "5") (pinfunction "+IN_B_5") (pintype "passive"))
    )
    (net (code "25") (name "Net-(U5-OUT_A)") (class "Default")
      (node (ref "R25") (pin "2") (pinfunction "2_2") (pintype "passive"))
      (node (ref "R26") (pin "2") (pinfunction "2_2") (pintype "passive"))
      (node (ref "U5") (pin "1") (pinfunction "OUT_A_1") (pintype "passive"))
    )
    (net (code "26") (name "Net-(U6-B1)") (class "Default")
      (node (ref "R25") (pin "1") (pinfunction "1_1") (pintype "passive"))
      (node (ref "U6") (pin "2") (pinfunction "B1_2") (pintype "passive"))
    )
    (net (code "27") (name "Net-(U6-B2)") (class "Default")
      (node (ref "R26") (pin "1") (pinfunction "1_1") (pintype "passive"))
      (node (ref "U6") (pin "5") (pinfunction "B2_5") (pintype "passive"))
    )
    (net (code "28") (name "Net-(U6-E1)") (class "Default")
      (node (ref "R27") (pin "2") (pinfunction "2_2") (pintype "passive"))
      (node (ref "U6") (pin "6") (pinfunction "E1_6") (pintype "passive"))
    )
    (net (code "29") (name "Net-(U6-E2)") (class "Default")
      (node (ref "R28") (pin "2") (pinfunction "2_2") (pintype "passive"))
      (node (ref "U6") (pin "4") (pinfunction "E2_4") (pintype "passive"))
    )
    (net (code "30") (name "Net-(U7-NFB)") (class "Default")
      (node (ref "C16") (pin "2") (pinfunction "2_2") (pintype "passive"))
      (node (ref "R29") (pin "1") (pinfunction "1_1") (pintype "passive"))
      (node (ref "R30") (pin "2") (pinfunction "2_2") (pintype "passive"))
      (node (ref "U7") (pin "3") (pinfunction "NFB_3") (pintype "input"))
    )
    (net (code "31") (name "Net-(U7-SW)") (class "Default")
      (node (ref "C15") (pin "1") (pinfunction "1_1") (pintype "passive"))
      (node (ref "L1") (pin "2") (pinfunction "2_2") (pintype "passive"))
      (node (ref "U7") (pin "1") (pinfunction "SW_1") (pintype "power_in"))
    )
    (net (code "32") (name "Net-(U8-SET)") (class "Default")
      (node (ref "C21") (pin "1") (pinfunction "1_1") (pintype "passive"))
      (node (ref "R32") (pin "1") (pinfunction "1_1") (pintype "passive"))
      (node (ref "U8") (pin "8") (pinfunction "SET_8") (pintype "passive"))
    )
    (net (code "33") (name "Net-(U10-TRIM{slash}NR)") (class "Default")
      (node (ref "C7") (pin "1") (pinfunction "1_1") (pintype "passive"))
      (node (ref "U10") (pin "5") (pinfunction "TRIM/NR_5") (pintype "passive"))
    )
    (net (code "34") (name "unconnected-(U3-PG-Pad5)") (class "Default")
      (node (ref "U3") (pin "5") (pinfunction "PG_5") (pintype "passive+no_connect"))
    )
    (net (code "35") (name "unconnected-(U8-PG-Pad4)") (class "Default")
      (node (ref "U8") (pin "4") (pinfunction "PG_4") (pintype "passive+no_connect"))
    )
    (net (code "36") (name "unconnected-(U8-VIOC-Pad7)") (class "Default")
      (node (ref "U8") (pin "7") (pinfunction "VIOC_7") (pintype "passive+no_connect"))
    )
    (net (code "37") (name "unconnected-(U10-DNC-Pad1)") (class "Default")
      (node (ref "U10") (pin "1") (pinfunction "DNC_1") (pintype "passive+no_connect"))
    )
    (net (code "38") (name "unconnected-(U10-DNC-Pad8)") (class "Default")
      (node (ref "U10") (pin "8") (pinfunction "DNC_8") (pintype "passive"))
    )
    (net (code "39") (name "unconnected-(U10-NC-Pad7)") (class "Default")
      (node (ref "U10") (pin "7") (pinfunction "NC_7") (pintype "passive+no_connect"))
    )
    (net (code "40") (name "unconnected-(U10-TEMP-Pad3)") (class "Default")
      (node (ref "U10") (pin "3") (pinfunction "TEMP_3") (pintype "passive"))
    )
  )
)
